# PT2262.net
KiCad netlist of a schematic drawn in Altium Designer
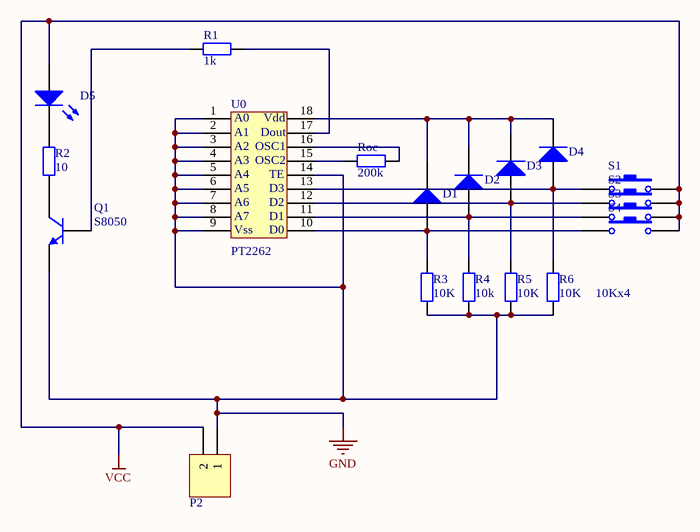
[diagram p0: PT2262.SchDoc]

(export (version "E")
  (design (tool "Eeschema 10.0.6"))
  (components
    (comp (ref "D1")
      (value "Diode")
      (footprint "DIODE4")
      (description "Default Diode")
      (fields (field (name "PUBLISHER") "Altium Limited"))
      (libsource (lib "Miscellaneous Devices") (part "Diode"))
    )
    (comp (ref "D2")
      (value "Diode")
      (footprint "DIODE4")
      (description "Default Diode")
      (fields (field (name "PUBLISHER") "Altium Limited"))
      (libsource (lib "Miscellaneous Devices") (part "Diode"))
    )
    (comp (ref "D3")
      (value "Diode")
      (footprint "DIODE4")
      (description "Default Diode")
      (fields (field (name "PUBLISHER") "Altium Limited"))
      (libsource (lib "Miscellaneous Devices") (part "Diode"))
    )
    (comp (ref "D4")
      (value "Diode")
      (footprint "DIODE4")
      (description "Default Diode")
      (fields (field (name "PUBLISHER") "Altium Limited"))
      (libsource (lib "Miscellaneous Devices") (part "Diode"))
    )
    (comp (ref "D5")
      (value "~")
      (footprint "LEDLXH-3")
      (description "Typical INFRARED GaAs LED")
      (fields (field (name "PUBLISHER") "Altium Limited"))
      (libsource (lib "Miscellaneous Devices") (part "LED0"))
    )
    (comp (ref "P2")
      (value "Header 2")
      (footprint "POWER PLUG2")
      (description "Header, 2-Pin")
      (fields (field (name "PUBLISHER") "Altium Limited"))
      (libsource (lib "Miscellaneous Connectors") (part "Header 2"))
    )
    (comp (ref "Q1")
      (value "S8050")
      (footprint "NPN-2")
      (description "NPN General Purpose Amplifier")
      (fields (field (name "PUBLISHER") "Altium Limited"))
      (libsource (lib "Miscellaneous Devices") (part "2N3904"))
    )
    (comp (ref "R1")
      (value "1k")
      (footprint "AXIAL-0.4")
      (description "Resistor")
      (fields (field (name "Comment") "Res2") (field (name "PUBLISHER") "Altium Limited"))
      (libsource (lib "Miscellaneous Devices") (part "Res2"))
    )
    (comp (ref "R2")
      (value "10")
      (footprint "AXIAL-0.4")
      (description "Resistor")
      (fields (field (name "Comment") "Res2") (field (name "PUBLISHER") "Altium Limited"))
      (libsource (lib "") (part "Res2_1"))
    )
    (comp (ref "R3")
      (value "10K")
      (footprint "AXIAL-0.4")
      (description "Resistor")
      (fields (field (name "Comment") "Res2") (field (name "PUBLISHER") "Altium Limited"))
      (libsource (lib "") (part "Res2_1"))
    )
    (comp (ref "R4")
      (value "10k")
      (footprint "AXIAL-0.4")
      (description "Resistor")
      (fields (field (name "Comment") "Res2") (field (name "PUBLISHER") "Altium Limited"))
      (libsource (lib "") (part "Res2_1"))
    )
    (comp (ref "R5")
      (value "10K")
      (footprint "AXIAL-0.4")
      (description "Resistor")
      (fields (field (name "Comment") "Res2") (field (name "PUBLISHER") "Altium Limited"))
      (libsource (lib "") (part "Res2_1"))
    )
    (comp (ref "R6")
      (value "10Kx4")
      (footprint "AXIAL-0.4")
      (description "Resistor")
      (fields (field (name "ALTIUM_VALUE") "10K") (field (name "PUBLISHER") "Altium Limited"))
      (libsource (lib "") (part "Res2_1"))
    )
    (comp (ref "Roc")
      (value "200k")
      (footprint "AXIAL-0.4")
      (description "Resistor")
      (fields (field (name "Comment") "Res2") (field (name "PUBLISHER") "Altium Limited"))
      (libsource (lib "") (part "Res2_2"))
    )
    (comp (ref "S1")
      (value "SW-PB")
      (footprint "AN-S")
      (description "Switch")
      (fields (field (name "PUBLISHER") "Altium Limited"))
      (libsource (lib "Miscellaneous Devices") (part "SW-PB"))
    )
    (comp (ref "S2")
      (value "SW-PB")
      (footprint "AN-S")
      (description "Switch")
      (fields (field (name "PUBLISHER") "Altium Limited"))
      (libsource (lib "Miscellaneous Devices") (part "SW-PB"))
    )
    (comp (ref "S3")
      (value "SW-PB")
      (footprint "AN-S")
      (description "Switch")
      (fields (field (name "PUBLISHER") "Altium Limited"))
      (libsource (lib "Miscellaneous Devices") (part "SW-PB"))
    )
    (comp (ref "S4")
      (value "SW-PB")
      (footprint "AN-S")
      (description "Switch")
      (fields (field (name "PUBLISHER") "Altium Limited"))
      (libsource (lib "Miscellaneous Devices") (part "SW-PB"))
    )
    (comp (ref "U0") (value "PT2262") (footprint "DIP-18") (libsource (lib "LixhSch") (part "PT2262")))
  )
  (nets
    (net (code "1") (name "GND") (class "Default")
      (node (ref "P2") (pin "1") (pinfunction "1_1") (pintype "passive"))
      (node (ref "Q1") (pin "1") (pinfunction "E_1") (pintype "passive"))
      (node (ref "R3") (pin "1") (pinfunction "1_1") (pintype "passive"))
      (node (ref "R4") (pin "1") (pinfunction "1_1") (pintype "passive"))
      (node (ref "R5") (pin "1") (pinfunction "1_1") (pintype "passive"))
      (node (ref "R6") (pin "1") (pinfunction "1_1") (pintype "passive"))
      (node (ref "U0") (pin "1") (pinfunction "1_1") (pintype "passive"))
      (node (ref "U0") (pin "14") (pinfunction "14_14") (pintype "passive"))
      (node (ref "U0") (pin "2") (pinfunction "2_2") (pintype "passive"))
      (node (ref "U0") (pin "3") (pinfunction "3_3") (pintype "passive"))
      (node (ref "U0") (pin "4") (pinfunction "4_4") (pintype "passive"))
      (node (ref "U0") (pin "5") (pinfunction "5_5") (pintype "passive"))
      (node (ref "U0") (pin "6") (pinfunction "6_6") (pintype "passive"))
      (node (ref "U0") (pin "7") (pinfunction "7_7") (pintype "passive"))
      (node (ref "U0") (pin "8") (pinfunction "8_8") (pintype "passive"))
      (node (ref "U0") (pin "9") (pinfunction "9_9") (pintype "passive"))
    )
    (net (code "2") (name "Net-(D1-A)") (class "Default")
      (node (ref "D1") (pin "1") (pinfunction "A_1") (pintype "passive"))
      (node (ref "R3") (pin "2") (pinfunction "2_2") (pintype "passive"))
      (node (ref "S4") (pin "1") (pinfunction "1_1") (pintype "passive"))
      (node (ref "U0") (pin "10") (pinfunction "10_10") (pintype "passive"))
    )
    (net (code "3") (name "Net-(D1-K)") (class "Default")
      (node (ref "D1") (pin "2") (pinfunction "K_2") (pintype "passive"))
      (node (ref "D2") (pin "2") (pinfunction "K_2") (pintype "passive"))
      (node (ref "D3") (pin "2") (pinfunction "K_2") (pintype "passive"))
      (node (ref "D4") (pin "2") (pinfunction "K_2") (pintype "passive"))
      (node (ref "U0") (pin "18") (pinfunction "18_18") (pintype "passive"))
    )
    (net (code "4") (name "Net-(D2-A)") (class "Default")
      (node (ref "D2") (pin "1") (pinfunction "A_1") (pintype "passive"))
      (node (ref "R4") (pin "2") (pinfunction "2_2") (pintype "passive"))
      (node (ref "S3") (pin "1") (pinfunction "1_1") (pintype "passive"))
      (node (ref "U0") (pin "11") (pinfunction "11_11") (pintype "passive"))
    )
    (net (code "5") (name "Net-(D3-A)") (class "Default")
      (node (ref "D3") (pin "1") (pinfunction "A_1") (pintype "passive"))
      (node (ref "R5") (pin "2") (pinfunction "2_2") (pintype "passive"))
      (node (ref "S2") (pin "1") (pinfunction "1_1") (pintype "passive"))
      (node (ref "U0") (pin "12") (pinfunction "12_12") (pintype "passive"))
    )
    (net (code "6") (name "Net-(D4-A)") (class "Default")
      (node (ref "D4") (pin "1") (pinfunction "A_1") (pintype "passive"))
      (node (ref "R6") (pin "2") (pinfunction "2_2") (pintype "passive"))
      (node (ref "S1") (pin "1") (pinfunction "1_1") (pintype "passive"))
      (node (ref "U0") (pin "13") (pinfunction "13_13") (pintype "passive"))
    )
    (net (code "7") (name "Net-(D5-K)") (class "Default")
      (node (ref "D5") (pin "2") (pinfunction "K_2") (pintype "passive"))
      (node (ref "R2") (pin "2") (pinfunction "2_2") (pintype "passive"))
    )
    (net (code "8") (name "Net-(Q1-B)") (class "Default")
      (node (ref "Q1") (pin "2") (pinfunction "B_2") (pintype "passive"))
      (node (ref "R1") (pin "1") (pinfunction "1_1") (pintype "passive"))
    )
    (net (code "9") (name "Net-(Q1-C)") (class "Default")
      (node (ref "Q1") (pin "3") (pinfunction "C_3") (pintype "passive"))
      (node (ref "R2") (pin "1") (pinfunction "1_1") (pintype "passive"))
    )
    (net (code "10") (name "Net-(R1-Pad2)") (class "Default")
      (node (ref "R1") (pin "2") (pinfunction "2_2") (pintype "passive"))
      (node (ref "U0") (pin "17") (pinfunction "17_17") (pintype "passive"))
    )
    (net (code "11") (name "Net-(Roc-Pad1)") (class "Default")
      (node (ref "Roc") (pin "1") (pinfunction "1_1") (pintype "passive"))
      (node (ref "U0") (pin "16") (pinfunction "16_16") (pintype "passive"))
    )
    (net (code "12") (name "Net-(Roc-Pad2)") (class "Default")
      (node (ref "Roc") (pin "2") (pinfunction "2_2") (pintype "passive"))
      (node (ref "U0") (pin "15") (pinfunction "15_15") (pintype "passive"))
    )
    (net (code "13") (name "VCC") (class "Default")
      (node (ref "D5") (pin "1") (pinfunction "A_1") (pintype "passive"))
      (node (ref "P2") (pin "2") (pinfunction "2_2") (pintype "passive"))
      (node (ref "S1") (pin "2") (pinfunction "2_2") (pintype "passive"))
      (node (ref "S2") (pin "2") (pinfunction "2_2") (pintype "passive"))
      (node (ref "S3") (pin "2") (pinfunction "2_2") (pintype "passive"))
      (node (ref "S4") (pin "2") (pinfunction "2_2") (pintype "passive"))
    )
  )
)
